# buck_automotive.net
KiCad netlist of a schematic drawn in Altium Designer
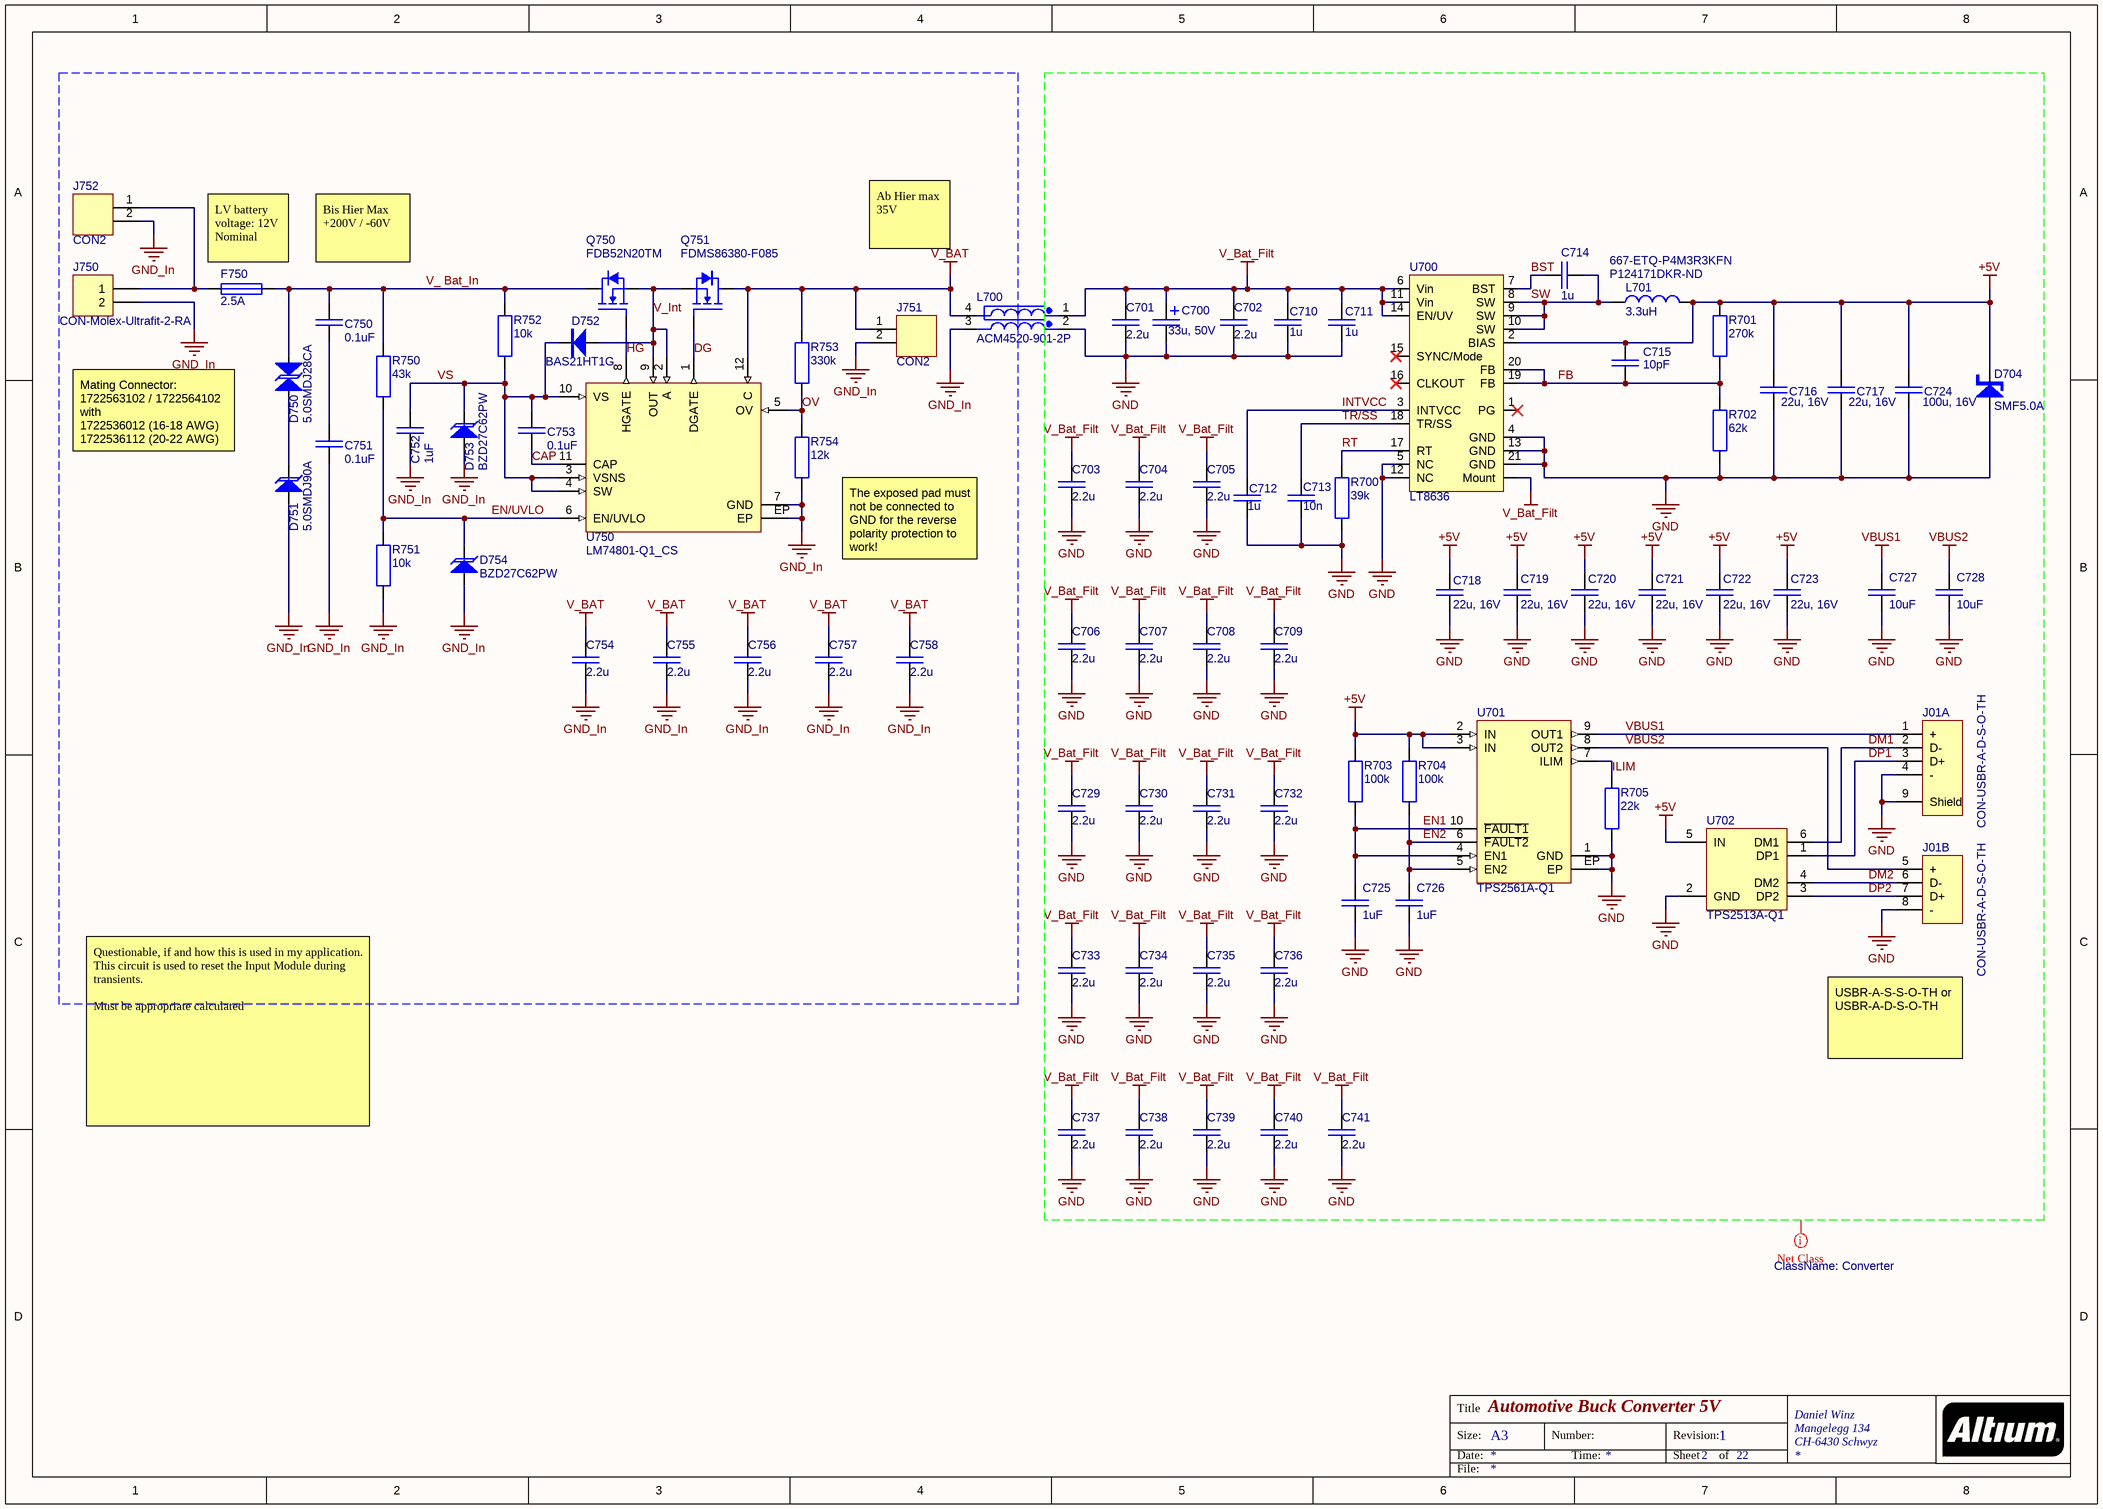
[diagram p0: buck_automotive.SchDoc]

(export (version "E")
  (design (tool "Eeschema 10.0.6"))
  (components
    (comp (ref "C700")
      (value "33u, 50V")
      (footprint "AHO_Altium_Lib:C_ELKO_SMD_6.6x6.6_7.7")
      (libsource (lib "AMZ_Altium_Lib") (part "C_Elko"))
    )
    (comp (ref "C701")
      (value "2.2u")
      (footprint "AHO_Altium_Lib:C_0805_S")
      (description "0805, 50V")
      (libsource (lib "AMZ_Altium_Lib") (part "C"))
    )
    (comp (ref "C702")
      (value "2.2u")
      (footprint "AHO_Altium_Lib:C_0805_S")
      (description "0805, 50V")
      (libsource (lib "AMZ_Altium_Lib") (part "C"))
    )
    (comp (ref "C703")
      (value "2.2u")
      (footprint "AHO_Altium_Lib:C_0805_S")
      (description "0805, 50V")
      (libsource (lib "AMZ_Altium_Lib") (part "C"))
    )
    (comp (ref "C704")
      (value "2.2u")
      (footprint "AHO_Altium_Lib:C_0805_S")
      (description "0805, 50V")
      (libsource (lib "AMZ_Altium_Lib") (part "C"))
    )
    (comp (ref "C705")
      (value "2.2u")
      (footprint "AHO_Altium_Lib:C_0805_S")
      (description "0805, 50V")
      (libsource (lib "AMZ_Altium_Lib") (part "C"))
    )
    (comp (ref "C706")
      (value "2.2u")
      (footprint "AHO_Altium_Lib:C_0805_S")
      (description "0805, 50V")
      (libsource (lib "AMZ_Altium_Lib") (part "C"))
    )
    (comp (ref "C707")
      (value "2.2u")
      (footprint "AHO_Altium_Lib:C_0805_S")
      (description "0805, 50V")
      (libsource (lib "AMZ_Altium_Lib") (part "C"))
    )
    (comp (ref "C708")
      (value "2.2u")
      (footprint "AHO_Altium_Lib:C_0805_S")
      (description "0805, 50V")
      (libsource (lib "AMZ_Altium_Lib") (part "C"))
    )
    (comp (ref "C709")
      (value "2.2u")
      (footprint "AHO_Altium_Lib:C_0805_S")
      (description "0805, 50V")
      (libsource (lib "AMZ_Altium_Lib") (part "C"))
    )
    (comp (ref "C710")
      (value "1u")
      (footprint "AHO_Altium_Lib:C_0603_S")
      (description "0603, >25V")
      (libsource (lib "AMZ_Altium_Lib") (part "C"))
    )
    (comp (ref "C711")
      (value "1u")
      (footprint "AHO_Altium_Lib:C_0603_S")
      (description "0603, >25V")
      (libsource (lib "AMZ_Altium_Lib") (part "C"))
    )
    (comp (ref "C712")
      (value "1u")
      (footprint "AHO_Altium_Lib:C_0603_S")
      (description "0603, >25V")
      (libsource (lib "AMZ_Altium_Lib") (part "C"))
    )
    (comp (ref "C713")
      (value "10n")
      (footprint "AHO_Altium_Lib:C_0603_S")
      (description "0603, >25V")
      (libsource (lib "AMZ_Altium_Lib") (part "C"))
    )
    (comp (ref "C714")
      (value "1u")
      (footprint "AHO_Altium_Lib:C_0603_S")
      (description "0603, >25V")
      (libsource (lib "AMZ_Altium_Lib") (part "C"))
    )
    (comp (ref "C715")
      (value "10pF")
      (footprint "AHO_Altium_Lib:C_0603_S")
      (description "0603, >25V")
      (libsource (lib "AMZ_Altium_Lib") (part "C"))
    )
    (comp (ref "C716")
      (value "22u, 16V")
      (footprint "AHO_Altium_Lib:C_1210_S")
      (description "10V 0805")
      (libsource (lib "AMZ_Altium_Lib") (part "C"))
    )
    (comp (ref "C717")
      (value "22u, 16V")
      (footprint "AHO_Altium_Lib:C_1210_S")
      (description "10V 0805")
      (libsource (lib "AMZ_Altium_Lib") (part "C"))
    )
    (comp (ref "C718")
      (value "22u, 16V")
      (footprint "AHO_Altium_Lib:C_1210_S")
      (description "10V 0805")
      (libsource (lib "AMZ_Altium_Lib") (part "C"))
    )
    (comp (ref "C719")
      (value "22u, 16V")
      (footprint "AHO_Altium_Lib:C_1210_S")
      (description "10V 0805")
      (libsource (lib "AMZ_Altium_Lib") (part "C"))
    )
    (comp (ref "C720")
      (value "22u, 16V")
      (footprint "AHO_Altium_Lib:C_1210_S")
      (description "10V 0805")
      (libsource (lib "AMZ_Altium_Lib") (part "C"))
    )
    (comp (ref "C721")
      (value "22u, 16V")
      (footprint "AHO_Altium_Lib:C_1210_S")
      (description "10V 0805")
      (libsource (lib "AMZ_Altium_Lib") (part "C"))
    )
    (comp (ref "C722")
      (value "22u, 16V")
      (footprint "AHO_Altium_Lib:C_1210_S")
      (description "10V 0805")
      (libsource (lib "AMZ_Altium_Lib") (part "C"))
    )
    (comp (ref "C723")
      (value "22u, 16V")
      (footprint "AHO_Altium_Lib:C_1210_S")
      (description "10V 0805")
      (libsource (lib "AMZ_Altium_Lib") (part "C"))
    )
    (comp (ref "C724")
      (value "100u, 16V")
      (footprint "AHO_Altium_Lib:C_ELKO_SMD_5.3X5.3_5.4")
      (description "10V ELKO")
      (libsource (lib "AMZ_Altium_Lib") (part "C"))
    )
    (comp (ref "C725")
      (value "1uF")
      (footprint "AHO_Altium_Lib:C_0603_S")
      (libsource (lib "AHO_Altium_Lib") (part "C"))
    )
    (comp (ref "C726")
      (value "1uF")
      (footprint "AHO_Altium_Lib:C_0603_S")
      (libsource (lib "AHO_Altium_Lib") (part "C"))
    )
    (comp (ref "C727")
      (value "10uF")
      (footprint "AHO_Altium_Lib:C_0805_S")
      (description "0805")
      (libsource (lib "AHO_Altium_Lib") (part "C"))
    )
    (comp (ref "C728")
      (value "10uF")
      (footprint "AHO_Altium_Lib:C_0805_S")
      (description "0805")
      (libsource (lib "AHO_Altium_Lib") (part "C"))
    )
    (comp (ref "C729")
      (value "2.2u")
      (footprint "AHO_Altium_Lib:C_0805_S")
      (description "0805, 50V")
      (libsource (lib "AMZ_Altium_Lib") (part "C"))
    )
    (comp (ref "C730")
      (value "2.2u")
      (footprint "AHO_Altium_Lib:C_0805_S")
      (description "0805, 50V")
      (libsource (lib "AMZ_Altium_Lib") (part "C"))
    )
    (comp (ref "C731")
      (value "2.2u")
      (footprint "AHO_Altium_Lib:C_0805_S")
      (description "0805, 50V")
      (libsource (lib "AMZ_Altium_Lib") (part "C"))
    )
    (comp (ref "C732")
      (value "2.2u")
      (footprint "AHO_Altium_Lib:C_0805_S")
      (description "0805, 50V")
      (libsource (lib "AMZ_Altium_Lib") (part "C"))
    )
    (comp (ref "C733")
      (value "2.2u")
      (footprint "AHO_Altium_Lib:C_0805_S")
      (description "0805, 50V")
      (libsource (lib "AMZ_Altium_Lib") (part "C"))
    )
    (comp (ref "C734")
      (value "2.2u")
      (footprint "AHO_Altium_Lib:C_0805_S")
      (description "0805, 50V")
      (libsource (lib "AMZ_Altium_Lib") (part "C"))
    )
    (comp (ref "C735")
      (value "2.2u")
      (footprint "AHO_Altium_Lib:C_0805_S")
      (description "0805, 50V")
      (libsource (lib "AMZ_Altium_Lib") (part "C"))
    )
    (comp (ref "C736")
      (value "2.2u")
      (footprint "AHO_Altium_Lib:C_0805_S")
      (description "0805, 50V")
      (libsource (lib "AMZ_Altium_Lib") (part "C"))
    )
    (comp (ref "C737")
      (value "2.2u")
      (footprint "AHO_Altium_Lib:C_0805_S")
      (description "0805, 50V")
      (libsource (lib "AMZ_Altium_Lib") (part "C"))
    )
    (comp (ref "C738")
      (value "2.2u")
      (footprint "AHO_Altium_Lib:C_0805_S")
      (description "0805, 50V")
      (libsource (lib "AMZ_Altium_Lib") (part "C"))
    )
    (comp (ref "C739")
      (value "2.2u")
      (footprint "AHO_Altium_Lib:C_0805_S")
      (description "0805, 50V")
      (libsource (lib "AMZ_Altium_Lib") (part "C"))
    )
    (comp (ref "C740")
      (value "2.2u")
      (footprint "AHO_Altium_Lib:C_0805_S")
      (description "0805, 50V")
      (libsource (lib "AMZ_Altium_Lib") (part "C"))
    )
    (comp (ref "C741")
      (value "2.2u")
      (footprint "AHO_Altium_Lib:C_0805_S")
      (description "0805, 50V")
      (libsource (lib "AMZ_Altium_Lib") (part "C"))
    )
    (comp (ref "C750")
      (value "0.1uF")
      (footprint "C_1206_S")
      (description "100V")
      (libsource (lib "AHO_Altium_Lib") (part "C"))
    )
    (comp (ref "C751")
      (value "0.1uF")
      (footprint "C_1206_S")
      (description "100V")
      (libsource (lib "AHO_Altium_Lib") (part "C"))
    )
    (comp (ref "C752")
      (value "1uF")
      (footprint "AHO_Altium_Lib:C_0603_S")
      (libsource (lib "AHO_Altium_Lib") (part "C"))
    )
    (comp (ref "C753")
      (value "0.1uF")
      (footprint "AHO_Altium_Lib:C_0603_S")
      (libsource (lib "AHO_Altium_Lib") (part "C"))
    )
    (comp (ref "C754")
      (value "2.2u")
      (footprint "AHO_Altium_Lib:C_0805_S")
      (description "0805, 50V")
      (libsource (lib "AMZ_Altium_Lib") (part "C"))
    )
    (comp (ref "C755")
      (value "2.2u")
      (footprint "AHO_Altium_Lib:C_0805_S")
      (description "0805, 50V")
      (libsource (lib "AMZ_Altium_Lib") (part "C"))
    )
    (comp (ref "C756")
      (value "2.2u")
      (footprint "AHO_Altium_Lib:C_0805_S")
      (description "0805, 50V")
      (libsource (lib "AMZ_Altium_Lib") (part "C"))
    )
    (comp (ref "C757")
      (value "2.2u")
      (footprint "AHO_Altium_Lib:C_0805_S")
      (description "0805, 50V")
      (libsource (lib "AMZ_Altium_Lib") (part "C"))
    )
    (comp (ref "C758")
      (value "2.2u")
      (footprint "AHO_Altium_Lib:C_0805_S")
      (description "0805, 50V")
      (libsource (lib "AMZ_Altium_Lib") (part "C"))
    )
    (comp (ref "D704")
      (value "SMF5.0A")
      (footprint "SOD123FL")
      (libsource (lib "AHO_Altium_Lib") (part "Schottky"))
    )
    (comp (ref "D750")
      (value "5.0SMDJ28CA")
      (footprint "AHO_Altium_Lib:DO-214AB")
      (libsource (lib "AHO_Altium_Lib") (part "TVS_BI"))
    )
    (comp (ref "D751")
      (value "5.0SMDJ90A")
      (footprint "AHO_Altium_Lib:DO-214AB")
      (libsource (lib "AHO_Altium_Lib") (part "TVS"))
    )
    (comp (ref "D752")
      (value "BAS21HT1G")
      (footprint "AHO_Altium_Lib:SOD-323")
      (description "Diode")
      (libsource (lib "AHO_Altium_Lib") (part "D?"))
    )
    (comp (ref "D753")
      (value "BZD27C62PW")
      (footprint "AHO_Altium_Lib:SOD123W")
      (libsource (lib "AHO_Altium_Lib") (part "TVS"))
    )
    (comp (ref "D754")
      (value "BZD27C62PW")
      (footprint "AHO_Altium_Lib:SOD123W")
      (libsource (lib "AHO_Altium_Lib") (part "TVS"))
    )
    (comp (ref "F750")
      (value "2.5A")
      (footprint "AHO_Altium_Lib:Littelfuse 157serie")
      (description "Fuse")
      (libsource (lib "AHO_Altium_Lib") (part "FUSE"))
    )
    (comp (ref "J01")
      (value "CON-USBR-A-D-S-O-TH")
      (footprint "buck_automotive_5v:CON-USBR-A-D-S-O-TH")
      (description "Samtec USBR-A-D-S-O-TH")
      (libsource (lib "buck_automotive_5v") (part "CON-USBR-A-D-S-O-TH"))
    )
    (comp (ref "J750")
      (value "CON-Molex-Ultrafit-2-RA")
      (footprint "buck_automotive_5v:CON-MOLEX-ULTRAFIT-172310-1X02")
      (description "Molex Ultrafit 2 pin Right-angle")
      (libsource (lib "buck_automotive_5v") (part "CON-Molex-Ultrafit-2-RA"))
    )
    (comp (ref "J751")
      (value "CON2")
      (footprint "HEADER_2_RM_2.54")
      (libsource (lib "AHO_Altium_Lib") (part "CON2"))
    )
    (comp (ref "J752") (value "CON2") (footprint "HEADER_2_RM_2.54") (libsource (lib "") (part "CON2_1")))
    (comp (ref "L700")
      (value "ACM4520-901-2P")
      (footprint "ACM4520-2P")
      (description "2 Phase Common Mode Choke")
      (libsource (lib "AHO_Altium_Lib") (part "L_2ph_cm_small"))
    )
    (comp (ref "L701")
      (value "3.3uH")
      (footprint "4020")
      (description "Inductor")
      (fields
        (field (name "SUPPLIER PART NUMBER 1") "P124171DKR-ND")
        (field (name "SUPPLIER PART NUMBER 2") "667-ETQ-P4M3R3KFN")
      )
      (libsource (lib "AHO_Altium_Lib") (part "L"))
    )
    (comp (ref "Q750")
      (value "FDB52N20TM")
      (footprint "AHO_Altium_Lib:TO-263-3-2")
      (libsource (lib "AHO_Altium_Lib") (part "MOSFET N"))
    )
    (comp (ref "Q751")
      (value "FDMS86380-F085")
      (footprint "AHO_Altium_Lib:SON5x6")
      (libsource (lib "") (part "MOSFET N_1"))
    )
    (comp (ref "R700")
      (value "39k")
      (footprint "AHO_Altium_Lib:R_0603_S")
      (description "Normaler Widerstand")
      (libsource (lib "AMZ_Altium_Lib") (part "R?"))
    )
    (comp (ref "R701")
      (value "270k")
      (footprint "AHO_Altium_Lib:R_0603_S")
      (description "Normaler Widerstand")
      (libsource (lib "AMZ_Altium_Lib") (part "R?"))
    )
    (comp (ref "R702")
      (value "62k")
      (footprint "AHO_Altium_Lib:R_0603_S")
      (description "Normaler Widerstand")
      (libsource (lib "AMZ_Altium_Lib") (part "R?"))
    )
    (comp (ref "R703")
      (value "100k")
      (footprint "AHO_Altium_Lib:R_0603_S")
      (description "Normaler Widerstand")
      (libsource (lib "AMZ_Altium_Lib") (part "R?"))
    )
    (comp (ref "R704")
      (value "100k")
      (footprint "AHO_Altium_Lib:R_0603_S")
      (description "Normaler Widerstand")
      (libsource (lib "AMZ_Altium_Lib") (part "R?"))
    )
    (comp (ref "R705")
      (value "22k")
      (footprint "AHO_Altium_Lib:R_0603_S")
      (description "Normaler Widerstand")
      (libsource (lib "AMZ_Altium_Lib") (part "R?"))
    )
    (comp (ref "R750")
      (value "43k")
      (footprint "AHO_Altium_Lib:R_0603_S")
      (description "Normaler Widerstand")
      (libsource (lib "AHO_Altium_Lib") (part "R"))
    )
    (comp (ref "R751")
      (value "10k")
      (footprint "AHO_Altium_Lib:R_0603_S")
      (description "Normaler Widerstand")
      (libsource (lib "AHO_Altium_Lib") (part "R"))
    )
    (comp (ref "R752")
      (value "10k")
      (footprint "AHO_Altium_Lib:R_0603_S")
      (description "Normaler Widerstand")
      (libsource (lib "AHO_Altium_Lib") (part "R"))
    )
    (comp (ref "R753")
      (value "330k")
      (footprint "AHO_Altium_Lib:R_0603_S")
      (description "Normaler Widerstand")
      (libsource (lib "AHO_Altium_Lib") (part "R"))
    )
    (comp (ref "R754")
      (value "12k")
      (footprint "AHO_Altium_Lib:R_0603_S")
      (description "Normaler Widerstand")
      (libsource (lib "AHO_Altium_Lib") (part "R"))
    )
    (comp (ref "U700")
      (value "LT8636")
      (footprint "LQFN_20_4x3")
      (description "42V, 5A/7A Peak Synchronous Step-Down Silent Switcher with 2.5μA Quiescent Current")
      (libsource (lib "AHO_Altium_Lib") (part "LT8636"))
    )
    (comp (ref "U701")
      (value "TPS2561A-Q1")
      (footprint "buck_automotive_5v:SON50P300X300X100-10-EP_TI-DRC010J")
      (description "TPS2561A-Q1 Dual Channel Precision Automotive Adjustable Current-Limited Power Switches")
      (libsource (lib "buck_automotive_5v") (part "TPS2561A-Q1"))
    )
    (comp (ref "U702")
      (value "TPS2513A-Q1")
      (footprint "buck_automotive_5v:SOT23-6P95_300X305X145L60")
      (description "TPS2513A-Q1 USB Dedicated Charging Port Controller")
      (libsource (lib "buck_automotive_5v") (part "TPS2513A-Q1"))
    )
    (comp (ref "U750")
      (value "LM74801-Q1_CS")
      (footprint "SON50P300X300X80-12-EP250X130X")
      (libsource (lib "AHO_Altium_Lib") (part "LM74801-Q1_CS"))
    )
  )
  (nets
    (net (code "1") (name "+5V") (class "Default")
      (node (ref "C715") (pin "2") (pinfunction "2_2") (pintype "passive"))
      (node (ref "C716") (pin "1") (pinfunction "1_1") (pintype "passive"))
      (node (ref "C717") (pin "1") (pinfunction "1_1") (pintype "passive"))
      (node (ref "C718") (pin "1") (pinfunction "1_1") (pintype "passive"))
      (node (ref "C719") (pin "1") (pinfunction "1_1") (pintype "passive"))
      (node (ref "C720") (pin "1") (pinfunction "1_1") (pintype "passive"))
      (node (ref "C721") (pin "1") (pinfunction "1_1") (pintype "passive"))
      (node (ref "C722") (pin "1") (pinfunction "1_1") (pintype "passive"))
      (node (ref "C723") (pin "1") (pinfunction "1_1") (pintype "passive"))
      (node (ref "C724") (pin "1") (pinfunction "1_1") (pintype "passive"))
      (node (ref "D704") (pin "K") (pinfunction "K_K") (pintype "passive"))
      (node (ref "L701") (pin "2") (pinfunction "2_2") (pintype "passive"))
      (node (ref "R701") (pin "1") (pintype "passive"))
      (node (ref "R703") (pin "1") (pintype "passive"))
      (node (ref "R704") (pin "1") (pintype "passive"))
      (node (ref "U700") (pin "2") (pinfunction "BIAS_2") (pintype "passive"))
      (node (ref "U701") (pin "2") (pinfunction "IN_2") (pintype "input"))
      (node (ref "U701") (pin "3") (pinfunction "IN_3") (pintype "input"))
      (node (ref "U702") (pin "5") (pinfunction "IN_5") (pintype "passive"))
    )
    (net (code "2") (name "/BST") (class "Default")
      (node (ref "C714") (pin "1") (pinfunction "1_1") (pintype "passive"))
      (node (ref "U700") (pin "7") (pinfunction "BST_7") (pintype "passive"))
    )
    (net (code "3") (name "/CAP") (class "Default")
      (node (ref "C753") (pin "2") (pinfunction "2_2") (pintype "passive"))
      (node (ref "U750") (pin "11") (pinfunction "CAP_11") (pintype "passive"))
    )
    (net (code "4") (name "/DG") (class "Default")
      (node (ref "Q751") (pin "G") (pinfunction "GATE_G") (pintype "passive"))
      (node (ref "U750") (pin "1") (pinfunction "DGATE_1") (pintype "output"))
    )
    (net (code "5") (name "/DM1") (class "Default")
      (node (ref "J01") (pin "2") (pinfunction "D-_2") (pintype "passive"))
      (node (ref "U702") (pin "6") (pinfunction "DM1_6") (pintype "passive"))
    )
    (net (code "6") (name "/DM2") (class "Default")
      (node (ref "J01") (pin "6") (pinfunction "D-_6") (pintype "passive"))
      (node (ref "U702") (pin "4") (pinfunction "DM2_4") (pintype "passive"))
    )
    (net (code "7") (name "/DP1") (class "Default")
      (node (ref "J01") (pin "3") (pinfunction "D+_3") (pintype "passive"))
      (node (ref "U702") (pin "1") (pinfunction "DP1_1") (pintype "passive"))
    )
    (net (code "8") (name "/DP2") (class "Default")
      (node (ref "J01") (pin "7") (pinfunction "D+_7") (pintype "passive"))
      (node (ref "U702") (pin "3") (pinfunction "DP2_3") (pintype "passive"))
    )
    (net (code "9") (name "/EN1") (class "Default")
      (node (ref "C725") (pin "2") (pinfunction "2_2") (pintype "passive"))
      (node (ref "R703") (pin "2") (pintype "passive"))
      (node (ref "U701") (pin "10") (pinfunction "~{FAULT1}_10") (pintype "open_collector"))
      (node (ref "U701") (pin "4") (pinfunction "EN1_4") (pintype "input"))
    )
    (net (code "10") (name "/EN2") (class "Default")
      (node (ref "C726") (pin "2") (pinfunction "2_2") (pintype "passive"))
      (node (ref "R704") (pin "2") (pintype "passive"))
      (node (ref "U701") (pin "5") (pinfunction "EN2_5") (pintype "input"))
      (node (ref "U701") (pin "6") (pinfunction "~{FAULT2}_6") (pintype "open_collector"))
    )
    (net (code "11") (name "/EN{slash}UVLO") (class "Default")
      (node (ref "D754") (pin "K") (pinfunction "K_K") (pintype "passive"))
      (node (ref "R750") (pin "2") (pintype "passive"))
      (node (ref "R751") (pin "1") (pintype "passive"))
      (node (ref "U750") (pin "6") (pinfunction "EN/UVLO_6") (pintype "input"))
    )
    (net (code "12") (name "/FB") (class "Default")
      (node (ref "C715") (pin "1") (pinfunction "1_1") (pintype "passive"))
      (node (ref "R701") (pin "2") (pintype "passive"))
      (node (ref "R702") (pin "1") (pintype "passive"))
      (node (ref "U700") (pin "19") (pinfunction "FB_19") (pintype "passive"))
      (node (ref "U700") (pin "20") (pinfunction "FB_20") (pintype "passive"))
    )
    (net (code "13") (name "/HG") (class "Default")
      (node (ref "Q750") (pin "1") (pinfunction "GATE_1") (pintype "passive"))
      (node (ref "U750") (pin "8") (pinfunction "HGATE_8") (pintype "output"))
    )
    (net (code "14") (name "/ILIM") (class "Default")
      (node (ref "R705") (pin "1") (pintype "passive"))
      (node (ref "U701") (pin "7") (pinfunction "ILIM_7") (pintype "output"))
    )
    (net (code "15") (name "/INTVCC") (class "Default")
      (node (ref "C712") (pin "1") (pinfunction "1_1") (pintype "passive"))
      (node (ref "U700") (pin "3") (pinfunction "INTVCC_3") (pintype "passive"))
    )
    (net (code "16") (name "/OV") (class "Default")
      (node (ref "R753") (pin "2") (pintype "passive"))
      (node (ref "R754") (pin "1") (pintype "passive"))
      (node (ref "U750") (pin "5") (pinfunction "OV_5") (pintype "input"))
    )
    (net (code "17") (name "/RT") (class "Default")
      (node (ref "R700") (pin "2") (pintype "passive"))
      (node (ref "U700") (pin "17") (pinfunction "RT_17") (pintype "passive"))
    )
    (net (code "18") (name "/SW") (class "Default")
      (node (ref "C714") (pin "2") (pinfunction "2_2") (pintype "passive"))
      (node (ref "L701") (pin "1") (pinfunction "1_1") (pintype "passive"))
      (node (ref "U700") (pin "10") (pinfunction "SW_10") (pintype "passive"))
      (node (ref "U700") (pin "8") (pinfunction "SW_8") (pintype "passive"))
      (node (ref "U700") (pin "9") (pinfunction "SW_9") (pintype "passive"))
    )
    (net (code "19") (name "/TR{slash}SS") (class "Default")
      (node (ref "C713") (pin "2") (pinfunction "2_2") (pintype "passive"))
      (node (ref "U700") (pin "18") (pinfunction "TR/SS_18") (pintype "passive"))
    )
    (net (code "20") (name "/VS") (class "Default")
      (node (ref "C752") (pin "2") (pinfunction "2_2") (pintype "passive"))
      (node (ref "C753") (pin "1") (pinfunction "1_1") (pintype "passive"))
      (node (ref "D752") (pin "K") (pinfunction "2_K") (pintype "passive"))
      (node (ref "D753") (pin "K") (pinfunction "K_K") (pintype "passive"))
      (node (ref "R752") (pin "2") (pintype "passive"))
      (node (ref "U750") (pin "10") (pinfunction "VS_10") (pintype "input"))
      (node (ref "U750") (pin "3") (pinfunction "VSNS_3") (pintype "input"))
      (node (ref "U750") (pin "4") (pinfunction "SW_4") (pintype "input"))
    )
    (net (code "21") (name "/V_ Bat_In") (class "Default")
      (node (ref "C750") (pin "1") (pinfunction "1_1") (pintype "passive"))
      (node (ref "D750") (pin "A") (pinfunction "A_A") (pintype "passive"))
      (node (ref "F750") (pin "2") (pintype "passive"))
      (node (ref "Q750") (pin "2") (pinfunction "DRAIN_2") (pintype "passive"))
      (node (ref "R750") (pin "1") (pintype "passive"))
      (node (ref "R752") (pin "1") (pintype "passive"))
    )
    (net (code "22") (name "/V_Int") (class "Default")
      (node (ref "D752") (pin "A") (pinfunction "1_A") (pintype "passive"))
      (node (ref "Q750") (pin "3") (pinfunction "SOURCE_3") (pintype "passive"))
      (node (ref "Q751") (pin "S") (pinfunction "SOURCE_S") (pintype "passive"))
      (node (ref "U750") (pin "2") (pinfunction "A_2") (pintype "input"))
      (node (ref "U750") (pin "9") (pinfunction "OUT_9") (pintype "input"))
    )
    (net (code "23") (name "GND") (class "Default")
      (node (ref "C700") (pin "2") (pinfunction "2_2") (pintype "passive"))
      (node (ref "C701") (pin "2") (pinfunction "2_2") (pintype "passive"))
      (node (ref "C702") (pin "2") (pinfunction "2_2") (pintype "passive"))
      (node (ref "C703") (pin "2") (pinfunction "2_2") (pintype "passive"))
      (node (ref "C704") (pin "2") (pinfunction "2_2") (pintype "passive"))
      (node (ref "C705") (pin "2") (pinfunction "2_2") (pintype "passive"))
      (node (ref "C706") (pin "2") (pinfunction "2_2") (pintype "passive"))
      (node (ref "C707") (pin "2") (pinfunction "2_2") (pintype "passive"))
      (node (ref "C708") (pin "2") (pinfunction "2_2") (pintype "passive"))
      (node (ref "C709") (pin "2") (pinfunction "2_2") (pintype "passive"))
      (node (ref "C710") (pin "1") (pinfunction "1_1") (pintype "passive"))
      (node (ref "C711") (pin "1") (pinfunction "1_1") (pintype "passive"))
      (node (ref "C712") (pin "2") (pinfunction "2_2") (pintype "passive"))
      (node (ref "C713") (pin "1") (pinfunction "1_1") (pintype "passive"))
      (node (ref "C716") (pin "2") (pinfunction "2_2") (pintype "passive"))
      (node (ref "C717") (pin "2") (pinfunction "2_2") (pintype "passive"))
      (node (ref "C718") (pin "2") (pinfunction "2_2") (pintype "passive"))
      (node (ref "C719") (pin "2") (pinfunction "2_2") (pintype "passive"))
      (node (ref "C720") (pin "2") (pinfunction "2_2") (pintype "passive"))
      (node (ref "C721") (pin "2") (pinfunction "2_2") (pintype "passive"))
      (node (ref "C722") (pin "2") (pinfunction "2_2") (pintype "passive"))
      (node (ref "C723") (pin "2") (pinfunction "2_2") (pintype "passive"))
      (node (ref "C724") (pin "2") (pinfunction "2_2") (pintype "passive"))
      (node (ref "C725") (pin "1") (pinfunction "1_1") (pintype "passive"))
      (node (ref "C726") (pin "1") (pinfunction "1_1") (pintype "passive"))
      (node (ref "C727") (pin "1") (pinfunction "1_1") (pintype "passive"))
      (node (ref "C728") (pin "1") (pinfunction "1_1") (pintype "passive"))
      (node (ref "C729") (pin "2") (pinfunction "2_2") (pintype "passive"))
      (node (ref "C730") (pin "2") (pinfunction "2_2") (pintype "passive"))
      (node (ref "C731") (pin "2") (pinfunction "2_2") (pintype "passive"))
      (node (ref "C732") (pin "2") (pinfunction "2_2") (pintype "passive"))
      (node (ref "C733") (pin "2") (pinfunction "2_2") (pintype "passive"))
      (node (ref "C734") (pin "2") (pinfunction "2_2") (pintype "passive"))
      (node (ref "C735") (pin "2") (pinfunction "2_2") (pintype "passive"))
      (node (ref "C736") (pin "2") (pinfunction "2_2") (pintype "passive"))
      (node (ref "C737") (pin "2") (pinfunction "2_2") (pintype "passive"))
      (node (ref "C738") (pin "2") (pinfunction "2_2") (pintype "passive"))
      (node (ref "C739") (pin "2") (pinfunction "2_2") (pintype "passive"))
      (node (ref "C740") (pin "2") (pinfunction "2_2") (pintype "passive"))
      (node (ref "C741") (pin "2") (pinfunction "2_2") (pintype "passive"))
      (node (ref "D704") (pin "A") (pinfunction "A_A") (pintype "passive"))
      (node (ref "J01") (pin "4") (pinfunction "-_4") (pintype "passive"))
      (node (ref "J01") (pin "8") (pinfunction "-_8") (pintype "passive"))
      (node (ref "J01") (pin "9") (pinfunction "Shield_9") (pintype "passive"))
      (node (ref "L700") (pin "2") (pinfunction "2_2") (pintype "passive"))
      (node (ref "R700") (pin "1") (pintype "passive"))
      (node (ref "R702") (pin "2") (pintype "passive"))
      (node (ref "R705") (pin "2") (pintype "passive"))
      (node (ref "U700") (pin "12") (pinfunction "NC_12") (pintype "passive"))
      (node (ref "U700") (pin "13") (pinfunction "GND_13") (pintype "passive"))
      (node (ref "U700") (pin "21") (pinfunction "GND_21") (pintype "passive"))
      (node (ref "U700") (pin "4") (pinfunction "GND_4") (pintype "passive"))
      (node (ref "U700") (pin "5") (pinfunction "NC_5") (pintype "passive"))
      (node (ref "U701") (pin "1") (pinfunction "GND_1") (pintype "passive"))
      (node (ref "U701") (pin "EP") (pinfunction "EP_EP") (pintype "passive"))
      (node (ref "U702") (pin "2") (pinfunction "GND_2") (pintype "passive"))
    )
    (net (code "24") (name "GND_In") (class "Default")
      (node (ref "C751") (pin "2") (pinfunction "2_2") (pintype "passive"))
      (node (ref "C752") (pin "1") (pinfunction "1_1") (pintype "passive"))
      (node (ref "C754") (pin "2") (pinfunction "2_2") (pintype "passive"))
      (node (ref "C755") (pin "2") (pinfunction "2_2") (pintype "passive"))
      (node (ref "C756") (pin "2") (pinfunction "2_2") (pintype "passive"))
      (node (ref "C757") (pin "2") (pinfunction "2_2") (pintype "passive"))
      (node (ref "C758") (pin "2") (pinfunction "2_2") (pintype "passive"))
      (node (ref "D751") (pin "A") (pinfunction "A_A") (pintype "passive"))
      (node (ref "D753") (pin "A") (pinfunction "A_A") (pintype "passive"))
      (node (ref "D754") (pin "A") (pinfunction "A_A") (pintype "passive"))
      (node (ref "J750") (pin "2") (pinfunction "2_2") (pintype "passive"))
      (node (ref "J751") (pin "2") (pintype "passive"))
      (node (ref "J752") (pin "2") (pintype "passive"))
      (node (ref "L700") (pin "3") (pinfunction "3_3") (pintype "passive"))
      (node (ref "R751") (pin "2") (pintype "passive"))
      (node (ref "R754") (pin "2") (pintype "passive"))
      (node (ref "U750") (pin "7") (pinfunction "GND_7") (pintype "passive"))
      (node (ref "U750") (pin "EP") (pinfunction "EP_EP") (pintype "passive"))
    )
    (net (code "25") (name "Net-(C750-Pad2)") (class "Default")
      (node (ref "C750") (pin "2") (pinfunction "2_2") (pintype "passive"))
      (node (ref "C751") (pin "1") (pinfunction "1_1") (pintype "passive"))
    )
    (net (code "26") (name "Net-(D750-PadK)") (class "Default")
      (node (ref "D750") (pin "K") (pinfunction "K_K") (pintype "passive"))
      (node (ref "D751") (pin "K") (pinfunction "K_K") (pintype "passive"))
    )
    (net (code "27") (name "Net-(F750-Pad1)") (class "Default")
      (node (ref "F750") (pin "1") (pintype "passive"))
      (node (ref "J750") (pin "1") (pinfunction "1_1") (pintype "passive"))
      (node (ref "J752") (pin "1") (pintype "passive"))
    )
    (net (code "28") (name "VBUS1") (class "Default")
      (node (ref "C727") (pin "2") (pinfunction "2_2") (pintype "passive"))
      (node (ref "J01") (pin "1") (pinfunction "+_1") (pintype "passive"))
      (node (ref "U701") (pin "9") (pinfunction "OUT1_9") (pintype "output"))
    )
    (net (code "29") (name "VBUS2") (class "Default")
      (node (ref "C728") (pin "2") (pinfunction "2_2") (pintype "passive"))
      (node (ref "J01") (pin "5") (pinfunction "+_5") (pintype "passive"))
      (node (ref "U701") (pin "8") (pinfunction "OUT2_8") (pintype "output"))
    )
    (net (code "30") (name "V_BAT") (class "Default")
      (node (ref "C754") (pin "1") (pinfunction "1_1") (pintype "passive"))
      (node (ref "C755") (pin "1") (pinfunction "1_1") (pintype "passive"))
      (node (ref "C756") (pin "1") (pinfunction "1_1") (pintype "passive"))
      (node (ref "C757") (pin "1") (pinfunction "1_1") (pintype "passive"))
      (node (ref "C758") (pin "1") (pinfunction "1_1") (pintype "passive"))
      (node (ref "J751") (pin "1") (pintype "passive"))
      (node (ref "L700") (pin "4") (pinfunction "4_4") (pintype "passive"))
      (node (ref "Q751") (pin "D") (pinfunction "DRAIN_D") (pintype "passive"))
      (node (ref "R753") (pin "1") (pintype "passive"))
      (node (ref "U750") (pin "12") (pinfunction "C_12") (pintype "input"))
    )
    (net (code "31") (name "V_Bat_Filt") (class "Default")
      (node (ref "C700") (pin "1") (pinfunction "1_1") (pintype "passive"))
      (node (ref "C701") (pin "1") (pinfunction "1_1") (pintype "passive"))
      (node (ref "C702") (pin "1") (pinfunction "1_1") (pintype "passive"))
      (node (ref "C703") (pin "1") (pinfunction "1_1") (pintype "passive"))
      (node (ref "C704") (pin "1") (pinfunction "1_1") (pintype "passive"))
      (node (ref "C705") (pin "1") (pinfunction "1_1") (pintype "passive"))
      (node (ref "C706") (pin "1") (pinfunction "1_1") (pintype "passive"))
      (node (ref "C707") (pin "1") (pinfunction "1_1") (pintype "passive"))
      (node (ref "C708") (pin "1") (pinfunction "1_1") (pintype "passive"))
      (node (ref "C709") (pin "1") (pinfunction "1_1") (pintype "passive"))
      (node (ref "C710") (pin "2") (pinfunction "2_2") (pintype "passive"))
      (node (ref "C711") (pin "2") (pinfunction "2_2") (pintype "passive"))
      (node (ref "C729") (pin "1") (pinfunction "1_1") (pintype "passive"))
      (node (ref "C730") (pin "1") (pinfunction "1_1") (pintype "passive"))
      (node (ref "C731") (pin "1") (pinfunction "1_1") (pintype "passive"))
      (node (ref "C732") (pin "1") (pinfunction "1_1") (pintype "passive"))
      (node (ref "C733") (pin "1") (pinfunction "1_1") (pintype "passive"))
      (node (ref "C734") (pin "1") (pinfunction "1_1") (pintype "passive"))
      (node (ref "C735") (pin "1") (pinfunction "1_1") (pintype "passive"))
      (node (ref "C736") (pin "1") (pinfunction "1_1") (pintype "passive"))
      (node (ref "C737") (pin "1") (pinfunction "1_1") (pintype "passive"))
      (node (ref "C738") (pin "1") (pinfunction "1_1") (pintype "passive"))
      (node (ref "C739") (pin "1") (pinfunction "1_1") (pintype "passive"))
      (node (ref "C740") (pin "1") (pinfunction "1_1") (pintype "passive"))
      (node (ref "C741") (pin "1") (pinfunction "1_1") (pintype "passive"))
      (node (ref "L700") (pin "1") (pinfunction "1_1") (pintype "passive"))
      (node (ref "U700") (pin "11") (pinfunction "Vin_11") (pintype "passive"))
      (node (ref "U700") (pin "14") (pinfunction "EN/UV_14") (pintype "passive"))
      (node (ref "U700") (pin "6") (pinfunction "Vin_6") (pintype "passive"))
      (node (ref "U700") (pin "M") (pinfunction "Mount_M") (pintype "passive"))
    )
    (net (code "32") (name "unconnected-(U700-CLKOUT-Pad16)") (class "Default")
      (node (ref "U700") (pin "16") (pinfunction "CLKOUT_16") (pintype "passive+no_connect"))
    )
    (net (code "33") (name "unconnected-(U700-PG-Pad1)") (class "Default")
      (node (ref "U700") (pin "1") (pinfunction "PG_1") (pintype "passive+no_connect"))
    )
    (net (code "34") (name "unconnected-(U700-SYNC{slash}Mode-Pad15)") (class "Default")
      (node (ref "U700") (pin "15") (pinfunction "SYNC/Mode_15") (pintype "passive+no_connect"))
    )
  )
)
